# publish1.net
KiCad netlist of a schematic drawn in EAGLE
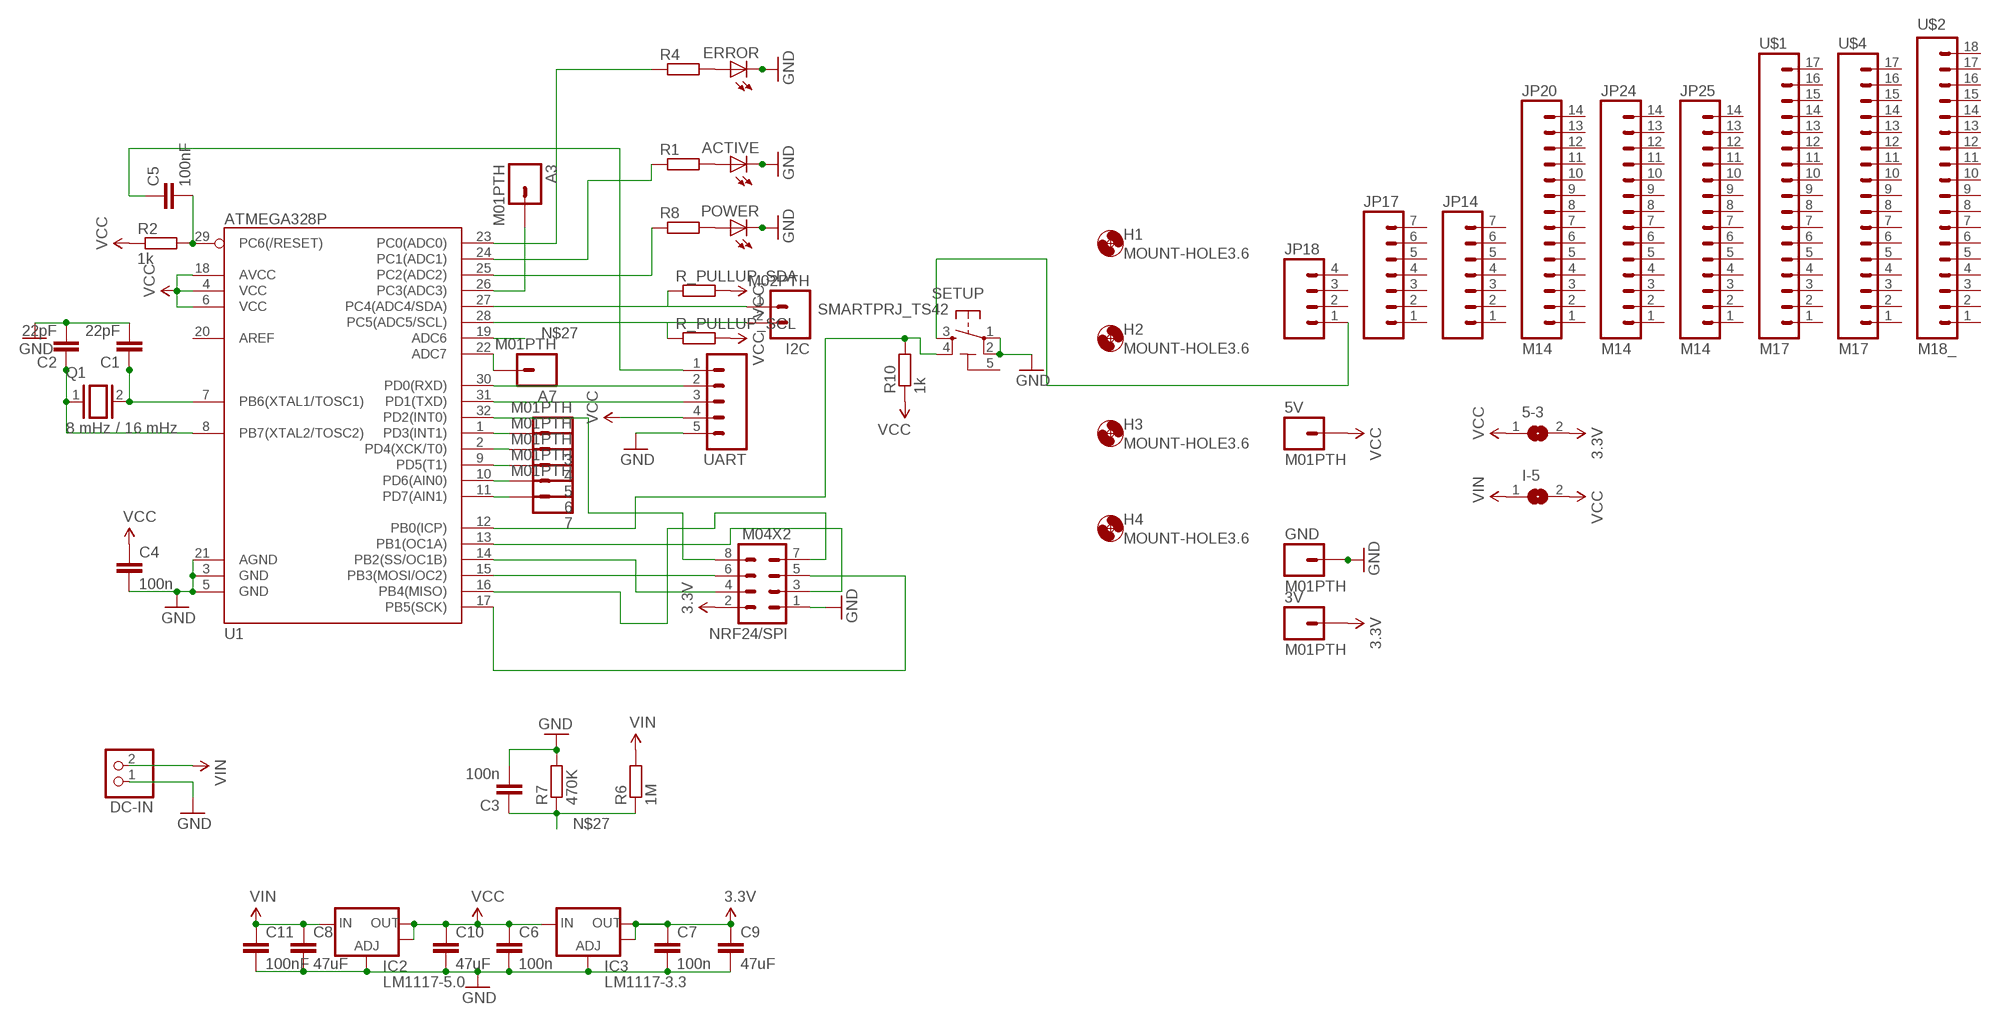
[diagram p0: schematic, sheet 1]

(export (version "E")
  (design (tool "Eeschema 10.0.6"))
  (components
    (comp (ref "3")
      (value "M01PTH")
      (footprint "eagle-import:1X01")
      (libsource (lib "eagle-import") (part "M01PTH"))
    )
    (comp (ref "3V")
      (value "M01PTH")
      (footprint "eagle-import:1X01")
      (libsource (lib "eagle-import") (part "M01PTH"))
    )
    (comp (ref "4")
      (value "M01PTH")
      (footprint "eagle-import:1X01")
      (libsource (lib "eagle-import") (part "M01PTH"))
    )
    (comp (ref "5")
      (value "M01PTH")
      (footprint "eagle-import:1X01")
      (libsource (lib "eagle-import") (part "M01PTH"))
    )
    (comp (ref "5-3")
      (value "JUMPER_SJ")
      (footprint "eagle-import:JUMPER_SJ")
      (libsource (lib "eagle-import") (part "JUMPER_SJ"))
    )
    (comp (ref "5V")
      (value "M01PTH")
      (footprint "eagle-import:1X01")
      (libsource (lib "eagle-import") (part "M01PTH"))
    )
    (comp (ref "6")
      (value "M01PTH")
      (footprint "eagle-import:1X01")
      (libsource (lib "eagle-import") (part "M01PTH"))
    )
    (comp (ref "7")
      (value "M01PTH")
      (footprint "eagle-import:1X01")
      (libsource (lib "eagle-import") (part "M01PTH"))
    )
    (comp (ref "A3")
      (value "M01PTH")
      (footprint "eagle-import:1X01")
      (libsource (lib "eagle-import") (part "M01PTH"))
    )
    (comp (ref "A7")
      (value "M01PTH")
      (footprint "eagle-import:1X01")
      (libsource (lib "eagle-import") (part "M01PTH"))
    )
    (comp (ref "ACTIVE")
      (value "LEDCHIP-LED0805")
      (footprint "eagle-import:CHIP-LED0805")
      (libsource (lib "eagle-import") (part "LEDCHIP-LED0805"))
    )
    (comp (ref "C1")
      (value "22pF")
      (footprint "eagle-import:C0805K")
      (libsource (lib "eagle-import") (part "C-EUC0805K"))
    )
    (comp (ref "C2")
      (value "22pF")
      (footprint "eagle-import:C0805K")
      (libsource (lib "eagle-import") (part "C-EUC0805K"))
    )
    (comp (ref "C3")
      (value "100n")
      (footprint "eagle-import:C0805K")
      (libsource (lib "eagle-import") (part "C-EUC0805K"))
    )
    (comp (ref "C4")
      (value "100n")
      (footprint "eagle-import:C0805K")
      (libsource (lib "eagle-import") (part "C-EUC0805K"))
    )
    (comp (ref "C5")
      (value "100nF")
      (footprint "eagle-import:C0805K")
      (libsource (lib "eagle-import") (part "C-EUC0805K"))
    )
    (comp (ref "C6")
      (value "100n")
      (footprint "eagle-import:C0805K")
      (libsource (lib "eagle-import") (part "C-EUC0805K"))
    )
    (comp (ref "C7")
      (value "100n")
      (footprint "eagle-import:C0805K")
      (libsource (lib "eagle-import") (part "C-EUC0805K"))
    )
    (comp (ref "C8")
      (value "47uF")
      (footprint "eagle-import:1210")
      (libsource (lib "eagle-import") (part "22UF-16V-20%-(1210)"))
    )
    (comp (ref "C9")
      (value "47uF")
      (footprint "eagle-import:1210")
      (libsource (lib "eagle-import") (part "22UF-16V-20%-(1210)"))
    )
    (comp (ref "C10")
      (value "47uF")
      (footprint "eagle-import:1210")
      (libsource (lib "eagle-import") (part "22UF-16V-20%-(1210)"))
    )
    (comp (ref "C11")
      (value "100nF")
      (footprint "eagle-import:C0805K")
      (libsource (lib "eagle-import") (part "C-EUC0805K"))
    )
    (comp (ref "DC-IN")
      (value "PINHD-1X2")
      (footprint "eagle-import:1X02")
      (libsource (lib "eagle-import") (part "PINHD-1X2"))
    )
    (comp (ref "ERROR")
      (value "LEDCHIP-LED0805")
      (footprint "eagle-import:CHIP-LED0805")
      (libsource (lib "eagle-import") (part "LEDCHIP-LED0805"))
    )
    (comp (ref "GND")
      (value "M01PTH")
      (footprint "eagle-import:1X01")
      (libsource (lib "eagle-import") (part "M01PTH"))
    )
    (comp (ref "H1")
      (value "MOUNT-HOLE3.6")
      (footprint "eagle-import:3,6")
      (libsource (lib "eagle-import") (part "MOUNT-HOLE3.6"))
    )
    (comp (ref "H2")
      (value "MOUNT-HOLE3.6")
      (footprint "eagle-import:3,6")
      (libsource (lib "eagle-import") (part "MOUNT-HOLE3.6"))
    )
    (comp (ref "H3")
      (value "MOUNT-HOLE3.6")
      (footprint "eagle-import:3,6")
      (libsource (lib "eagle-import") (part "MOUNT-HOLE3.6"))
    )
    (comp (ref "H4")
      (value "MOUNT-HOLE3.6")
      (footprint "eagle-import:3,6")
      (libsource (lib "eagle-import") (part "MOUNT-HOLE3.6"))
    )
    (comp (ref "I-5")
      (value "JUMPER_SJ")
      (footprint "eagle-import:JUMPER_SJ")
      (libsource (lib "eagle-import") (part "JUMPER_SJ"))
    )
    (comp (ref "I2C")
      (value "M02PTH")
      (footprint "eagle-import:1X02")
      (libsource (lib "eagle-import") (part "M02PTH"))
    )
    (comp (ref "IC2")
      (value "LM1117-5.0")
      (footprint "eagle-import:SOT223")
      (libsource (lib "eagle-import") (part "V_REG_LM1117SOT223"))
    )
    (comp (ref "IC3")
      (value "LM1117-3.3")
      (footprint "eagle-import:SOT223")
      (libsource (lib "eagle-import") (part "V_REG_LM1117SOT223"))
    )
    (comp (ref "JP14")
      (value "M07")
      (footprint "eagle-import:1X07")
      (libsource (lib "eagle-import") (part "M07"))
    )
    (comp (ref "JP17")
      (value "M07")
      (footprint "eagle-import:1X07")
      (libsource (lib "eagle-import") (part "M07"))
    )
    (comp (ref "JP18")
      (value "M04PTH")
      (footprint "eagle-import:1X04")
      (libsource (lib "eagle-import") (part "M04PTH"))
    )
    (comp (ref "JP20")
      (value "M14")
      (footprint "eagle-import:1X14")
      (libsource (lib "eagle-import") (part "M14"))
    )
    (comp (ref "JP24")
      (value "M14")
      (footprint "eagle-import:1X14")
      (libsource (lib "eagle-import") (part "M14"))
    )
    (comp (ref "JP25")
      (value "M14")
      (footprint "eagle-import:1X14")
      (libsource (lib "eagle-import") (part "M14"))
    )
    (comp (ref "NRF24/SPI")
      (value "M04X2")
      (footprint "eagle-import:2X4")
      (libsource (lib "eagle-import") (part "M04X2"))
    )
    (comp (ref "POWER")
      (value "LEDCHIP-LED0805")
      (footprint "eagle-import:CHIP-LED0805")
      (libsource (lib "eagle-import") (part "LEDCHIP-LED0805"))
    )
    (comp (ref "Q1")
      (value "8 mHz / 16 mHz")
      (footprint "eagle-import:QS")
      (libsource (lib "eagle-import") (part "XTAL/S"))
    )
    (comp (ref "R1")
      (value "SMARTPRJ_R-EU_M0805")
      (footprint "eagle-import:SMARTPRJ_M0805")
      (libsource (lib "eagle-import") (part "SMARTPRJ_R-EU_M0805"))
    )
    (comp (ref "R2")
      (value "1k")
      (footprint "eagle-import:SMARTPRJ_M0805")
      (libsource (lib "eagle-import") (part "SMARTPRJ_R-EU_M0805"))
    )
    (comp (ref "R4")
      (value "SMARTPRJ_R-EU_M0805")
      (footprint "eagle-import:SMARTPRJ_M0805")
      (libsource (lib "eagle-import") (part "SMARTPRJ_R-EU_M0805"))
    )
    (comp (ref "R6")
      (value "1M")
      (footprint "eagle-import:SMARTPRJ_M0805")
      (libsource (lib "eagle-import") (part "SMARTPRJ_R-EU_M0805"))
    )
    (comp (ref "R7")
      (value "470K")
      (footprint "eagle-import:SMARTPRJ_M0805")
      (libsource (lib "eagle-import") (part "SMARTPRJ_R-EU_M0805"))
    )
    (comp (ref "R8")
      (value "SMARTPRJ_R-EU_M0805")
      (footprint "eagle-import:SMARTPRJ_M0805")
      (libsource (lib "eagle-import") (part "SMARTPRJ_R-EU_M0805"))
    )
    (comp (ref "R10")
      (value "1k")
      (footprint "eagle-import:SMARTPRJ_M0805")
      (libsource (lib "eagle-import") (part "SMARTPRJ_R-EU_M0805"))
    )
    (comp (ref "R_PULLUP_SCL")
      (value "SMARTPRJ_R-EU_M0805")
      (footprint "eagle-import:SMARTPRJ_M0805")
      (libsource (lib "eagle-import") (part "SMARTPRJ_R-EU_M0805"))
    )
    (comp (ref "R_PULLUP_SDA")
      (value "SMARTPRJ_R-EU_M0805")
      (footprint "eagle-import:SMARTPRJ_M0805")
      (libsource (lib "eagle-import") (part "SMARTPRJ_R-EU_M0805"))
    )
    (comp (ref "SETUP")
      (value "SMARTPRJ_TS42")
      (footprint "eagle-import:SMARTPRJ_TS42")
      (libsource (lib "eagle-import") (part "SMARTPRJ_TS42"))
    )
    (comp (ref "U$1")
      (value "M17")
      (footprint "eagle-import:1X17")
      (libsource (lib "eagle-import") (part "M17"))
    )
    (comp (ref "U$2")
      (value "M18_")
      (footprint "eagle-import:1X18")
      (libsource (lib "eagle-import") (part "M18_"))
    )
    (comp (ref "U$4")
      (value "M17")
      (footprint "eagle-import:1X17")
      (libsource (lib "eagle-import") (part "M17"))
    )
    (comp (ref "U1")
      (value "ATMEGA328P")
      (footprint "eagle-import:TQFP32-08")
      (libsource (lib "eagle-import") (part "ATMEGA328_SMT"))
    )
    (comp (ref "UART")
      (value "M05PTH")
      (footprint "eagle-import:1X05")
      (libsource (lib "eagle-import") (part "M05PTH"))
    )
  )
  (nets
    (net (code "1") (name "/5-GND") (class "Default")
      (node (ref "SETUP") (pin "5") (pinfunction "5-GND_5") (pintype "power_in"))
    )
    (net (code "2") (name "/N$27") (class "Default")
      (node (ref "C3") (pin "1") (pinfunction "1_1") (pintype "passive"))
      (node (ref "R6") (pin "1") (pinfunction "1_1") (pintype "passive"))
      (node (ref "R7") (pin "1") (pinfunction "1_1") (pintype "passive"))
      (node (ref "U1") (pin "19") (pinfunction "ADC6_19") (pintype "bidirectional"))
    )
    (net (code "3") (name "3.3V") (class "Default")
      (node (ref "3V") (pin "1") (pinfunction "1_1") (pintype "passive"))
      (node (ref "5-3") (pin "2") (pinfunction "2_2") (pintype "passive"))
      (node (ref "C7") (pin "1") (pinfunction "1_1") (pintype "passive"))
      (node (ref "C9") (pin "1") (pinfunction "1_1") (pintype "passive"))
      (node (ref "IC3") (pin "2") (pinfunction "OUT_2") (pintype "output"))
      (node (ref "IC3") (pin "4") (pinfunction "OUT_4") (pintype "output"))
      (node (ref "NRF24/SPI") (pin "2") (pinfunction "2_2") (pintype "passive"))
    )
    (net (code "4") (name "GND") (class "Default")
      (node (ref "ACTIVE") (pin "C") (pinfunction "C_C") (pintype "passive"))
      (node (ref "C1") (pin "2") (pinfunction "2_2") (pintype "passive"))
      (node (ref "C10") (pin "2") (pinfunction "2_2") (pintype "passive"))
      (node (ref "C11") (pin "2") (pinfunction "2_2") (pintype "passive"))
      (node (ref "C2") (pin "2") (pinfunction "2_2") (pintype "passive"))
      (node (ref "C3") (pin "2") (pinfunction "2_2") (pintype "passive"))
      (node (ref "C4") (pin "2") (pinfunction "2_2") (pintype "passive"))
      (node (ref "C6") (pin "2") (pinfunction "2_2") (pintype "passive"))
      (node (ref "C7") (pin "2") (pinfunction "2_2") (pintype "passive"))
      (node (ref "C8") (pin "2") (pinfunction "2_2") (pintype "passive"))
      (node (ref "C9") (pin "2") (pinfunction "2_2") (pintype "passive"))
      (node (ref "DC-IN") (pin "1") (pinfunction "1_1") (pintype "passive"))
      (node (ref "ERROR") (pin "C") (pinfunction "C_C") (pintype "passive"))
      (node (ref "GND") (pin "1") (pinfunction "1_1") (pintype "passive"))
      (node (ref "IC2") (pin "1") (pinfunction "ADJ_1") (pintype "input"))
      (node (ref "IC3") (pin "1") (pinfunction "ADJ_1") (pintype "input"))
      (node (ref "NRF24/SPI") (pin "1") (pinfunction "1_1") (pintype "passive"))
      (node (ref "POWER") (pin "C") (pinfunction "C_C") (pintype "passive"))
      (node (ref "R7") (pin "2") (pinfunction "2_2") (pintype "passive"))
      (node (ref "SETUP") (pin "1") (pinfunction "1_1") (pintype "passive"))
      (node (ref "SETUP") (pin "2") (pinfunction "2_2") (pintype "passive"))
      (node (ref "U1") (pin "21") (pinfunction "AGND_21") (pintype "bidirectional"))
      (node (ref "U1") (pin "3") (pinfunction "GND_3") (pintype "bidirectional"))
      (node (ref "U1") (pin "5") (pinfunction "GND_5") (pintype "bidirectional"))
      (node (ref "UART") (pin "5") (pinfunction "5_5") (pintype "passive"))
    )
    (net (code "5") (name "Net-(ACTIVE-PadA)") (class "Default")
      (node (ref "ACTIVE") (pin "A") (pinfunction "A_A") (pintype "passive"))
      (node (ref "R1") (pin "2") (pinfunction "2_2") (pintype "passive"))
    )
    (net (code "6") (name "Net-(C5-Pad1)") (class "Default")
      (node (ref "C5") (pin "1") (pinfunction "1_1") (pintype "passive"))
      (node (ref "UART") (pin "1") (pinfunction "1_1") (pintype "passive"))
    )
    (net (code "7") (name "Net-(ERROR-PadA)") (class "Default")
      (node (ref "ERROR") (pin "A") (pinfunction "A_A") (pintype "passive"))
      (node (ref "R4") (pin "2") (pinfunction "2_2") (pintype "passive"))
    )
    (net (code "8") (name "Net-(JP18-Pad1)") (class "Default")
      (node (ref "JP18") (pin "1") (pinfunction "1_1") (pintype "passive"))
      (node (ref "SETUP") (pin "3") (pinfunction "3_3") (pintype "passive"))
    )
    (net (code "9") (name "Net-(POWER-PadA)") (class "Default")
      (node (ref "POWER") (pin "A") (pinfunction "A_A") (pintype "passive"))
      (node (ref "R8") (pin "2") (pinfunction "2_2") (pintype "passive"))
    )
    (net (code "10") (name "Net-(U1-ADC7)") (class "Default")
      (node (ref "A7") (pin "1") (pinfunction "1_1") (pintype "passive"))
      (node (ref "U1") (pin "22") (pinfunction "ADC7_22") (pintype "bidirectional"))
    )
    (net (code "11") (name "Net-(U1-PB0(ICP))") (class "Default")
      (node (ref "R10") (pin "2") (pinfunction "2_2") (pintype "passive"))
      (node (ref "SETUP") (pin "4") (pinfunction "4_4") (pintype "passive"))
      (node (ref "U1") (pin "12") (pinfunction "PB0(ICP)_12") (pintype "bidirectional"))
    )
    (net (code "12") (name "Net-(U1-PB1(OC1A))") (class "Default")
      (node (ref "NRF24/SPI") (pin "3") (pinfunction "3_3") (pintype "passive"))
      (node (ref "U1") (pin "13") (pinfunction "PB1(OC1A)_13") (pintype "bidirectional"))
    )
    (net (code "13") (name "Net-(U1-PB2(SS{slash}OC1B))") (class "Default")
      (node (ref "NRF24/SPI") (pin "4") (pinfunction "4_4") (pintype "passive"))
      (node (ref "U1") (pin "14") (pinfunction "PB2(SS/OC1B)_14") (pintype "bidirectional"))
    )
    (net (code "14") (name "Net-(U1-PB3(MOSI{slash}OC2))") (class "Default")
      (node (ref "NRF24/SPI") (pin "6") (pinfunction "6_6") (pintype "passive"))
      (node (ref "U1") (pin "15") (pinfunction "PB3(MOSI/OC2)_15") (pintype "bidirectional"))
    )
    (net (code "15") (name "Net-(U1-PB4(MISO))") (class "Default")
      (node (ref "NRF24/SPI") (pin "7") (pinfunction "7_7") (pintype "passive"))
      (node (ref "U1") (pin "16") (pinfunction "PB4(MISO)_16") (pintype "bidirectional"))
    )
    (net (code "16") (name "Net-(U1-PB5(SCK))") (class "Default")
      (node (ref "NRF24/SPI") (pin "5") (pinfunction "5_5") (pintype "passive"))
      (node (ref "U1") (pin "17") (pinfunction "PB5(SCK)_17") (pintype "bidirectional"))
    )
    (net (code "17") (name "Net-(U1-PB6(XTAL1{slash}TOSC1))") (class "Default")
      (node (ref "C1") (pin "1") (pinfunction "1_1") (pintype "passive"))
      (node (ref "Q1") (pin "2") (pinfunction "2_2") (pintype "passive"))
      (node (ref "U1") (pin "7") (pinfunction "PB6(XTAL1/TOSC1)_7") (pintype "bidirectional"))
    )
    (net (code "18") (name "Net-(U1-PB7(XTAL2{slash}TOSC2))") (class "Default")
      (node (ref "C2") (pin "1") (pinfunction "1_1") (pintype "passive"))
      (node (ref "Q1") (pin "1") (pinfunction "1_1") (pintype "passive"))
      (node (ref "U1") (pin "8") (pinfunction "PB7(XTAL2/TOSC2)_8") (pintype "bidirectional"))
    )
    (net (code "19") (name "Net-(U1-PC0(ADC0))") (class "Default")
      (node (ref "R4") (pin "1") (pinfunction "1_1") (pintype "passive"))
      (node (ref "U1") (pin "23") (pinfunction "PC0(ADC0)_23") (pintype "bidirectional"))
    )
    (net (code "20") (name "Net-(U1-PC1(ADC1))") (class "Default")
      (node (ref "R1") (pin "1") (pinfunction "1_1") (pintype "passive"))
      (node (ref "U1") (pin "24") (pinfunction "PC1(ADC1)_24") (pintype "bidirectional"))
    )
    (net (code "21") (name "Net-(U1-PC2(ADC2))") (class "Default")
      (node (ref "R8") (pin "1") (pinfunction "1_1") (pintype "passive"))
      (node (ref "U1") (pin "25") (pinfunction "PC2(ADC2)_25") (pintype "bidirectional"))
    )
    (net (code "22") (name "Net-(U1-PC3(ADC3))") (class "Default")
      (node (ref "A3") (pin "1") (pinfunction "1_1") (pintype "passive"))
      (node (ref "U1") (pin "26") (pinfunction "PC3(ADC3)_26") (pintype "bidirectional"))
    )
    (net (code "23") (name "Net-(U1-PC4(ADC4{slash}SDA))") (class "Default")
      (node (ref "I2C") (pin "1") (pinfunction "1_1") (pintype "passive"))
      (node (ref "R_PULLUP_SDA") (pin "1") (pinfunction "1_1") (pintype "passive"))
      (node (ref "U1") (pin "27") (pinfunction "PC4(ADC4/SDA)_27") (pintype "bidirectional"))
    )
    (net (code "24") (name "Net-(U1-PC5(ADC5{slash}SCL))") (class "Default")
      (node (ref "I2C") (pin "2") (pinfunction "2_2") (pintype "passive"))
      (node (ref "R_PULLUP_SCL") (pin "1") (pinfunction "1_1") (pintype "passive"))
      (node (ref "U1") (pin "28") (pinfunction "PC5(ADC5/SCL)_28") (pintype "bidirectional"))
    )
    (net (code "25") (name "Net-(U1-PC6({slash}RESET))") (class "Default")
      (node (ref "C5") (pin "2") (pinfunction "2_2") (pintype "passive"))
      (node (ref "R2") (pin "2") (pinfunction "2_2") (pintype "passive"))
      (node (ref "U1") (pin "29") (pinfunction "PC6(/RESET)_29") (pintype "bidirectional"))
    )
    (net (code "26") (name "Net-(U1-PD0(RXD))") (class "Default")
      (node (ref "U1") (pin "30") (pinfunction "PD0(RXD)_30") (pintype "bidirectional"))
      (node (ref "UART") (pin "2") (pinfunction "2_2") (pintype "passive"))
    )
    (net (code "27") (name "Net-(U1-PD1(TXD))") (class "Default")
      (node (ref "U1") (pin "31") (pinfunction "PD1(TXD)_31") (pintype "bidirectional"))
      (node (ref "UART") (pin "3") (pinfunction "3_3") (pintype "passive"))
    )
    (net (code "28") (name "Net-(U1-PD2(INT0))") (class "Default")
      (node (ref "NRF24/SPI") (pin "8") (pinfunction "8_8") (pintype "passive"))
      (node (ref "U1") (pin "32") (pinfunction "PD2(INT0)_32") (pintype "bidirectional"))
    )
    (net (code "29") (name "Net-(U1-PD3(INT1))") (class "Default")
      (node (ref "3") (pin "1") (pinfunction "1_1") (pintype "passive"))
      (node (ref "U1") (pin "1") (pinfunction "PD3(INT1)_1") (pintype "bidirectional"))
    )
    (net (code "30") (name "Net-(U1-PD4(XCK{slash}T0))") (class "Default")
      (node (ref "4") (pin "1") (pinfunction "1_1") (pintype "passive"))
      (node (ref "U1") (pin "2") (pinfunction "PD4(XCK/T0)_2") (pintype "bidirectional"))
    )
    (net (code "31") (name "Net-(U1-PD5(T1))") (class "Default")
      (node (ref "5") (pin "1") (pinfunction "1_1") (pintype "passive"))
      (node (ref "U1") (pin "9") (pinfunction "PD5(T1)_9") (pintype "bidirectional"))
    )
    (net (code "32") (name "Net-(U1-PD6(AIN0))") (class "Default")
      (node (ref "6") (pin "1") (pinfunction "1_1") (pintype "passive"))
      (node (ref "U1") (pin "10") (pinfunction "PD6(AIN0)_10") (pintype "bidirectional"))
    )
    (net (code "33") (name "Net-(U1-PD7(AIN1))") (class "Default")
      (node (ref "7") (pin "1") (pinfunction "1_1") (pintype "passive"))
      (node (ref "U1") (pin "11") (pinfunction "PD7(AIN1)_11") (pintype "bidirectional"))
    )
    (net (code "34") (name "VCC") (class "Default")
      (node (ref "5-3") (pin "1") (pinfunction "1_1") (pintype "passive"))
      (node (ref "5V") (pin "1") (pinfunction "1_1") (pintype "passive"))
      (node (ref "C10") (pin "1") (pinfunction "1_1") (pintype "passive"))
      (node (ref "C4") (pin "1") (pinfunction "1_1") (pintype "passive"))
      (node (ref "C6") (pin "1") (pinfunction "1_1") (pintype "passive"))
      (node (ref "I-5") (pin "2") (pinfunction "2_2") (pintype "passive"))
      (node (ref "IC2") (pin "2") (pinfunction "OUT_2") (pintype "output"))
      (node (ref "IC2") (pin "4") (pinfunction "OUT_4") (pintype "output"))
      (node (ref "IC3") (pin "3") (pinfunction "IN_3") (pintype "input"))
      (node (ref "R10") (pin "1") (pinfunction "1_1") (pintype "passive"))
      (node (ref "R2") (pin "1") (pinfunction "1_1") (pintype "passive"))
      (node (ref "R_PULLUP_SCL") (pin "2") (pinfunction "2_2") (pintype "passive"))
      (node (ref "R_PULLUP_SDA") (pin "2") (pinfunction "2_2") (pintype "passive"))
      (node (ref "U1") (pin "18") (pinfunction "AVCC_18") (pintype "bidirectional"))
      (node (ref "U1") (pin "4") (pinfunction "VCC_4") (pintype "bidirectional"))
      (node (ref "U1") (pin "6") (pinfunction "VCC_6") (pintype "bidirectional"))
      (node (ref "UART") (pin "4") (pinfunction "4_4") (pintype "passive"))
    )
    (net (code "35") (name "VIN") (class "Default")
      (node (ref "C11") (pin "1") (pinfunction "1_1") (pintype "passive"))
      (node (ref "C8") (pin "1") (pinfunction "1_1") (pintype "passive"))
      (node (ref "DC-IN") (pin "2") (pinfunction "2_2") (pintype "passive"))
      (node (ref "I-5") (pin "1") (pinfunction "1_1") (pintype "passive"))
      (node (ref "IC2") (pin "3") (pinfunction "IN_3") (pintype "input"))
      (node (ref "R6") (pin "2") (pinfunction "2_2") (pintype "passive"))
    )
    (net (code "36") (name "unconnected-(JP14-Pad1)") (class "Default")
      (node (ref "JP14") (pin "1") (pinfunction "1_1") (pintype "passive"))
    )
    (net (code "37") (name "unconnected-(JP14-Pad2)") (class "Default")
      (node (ref "JP14") (pin "2") (pinfunction "2_2") (pintype "passive"))
    )
    (net (code "38") (name "unconnected-(JP14-Pad3)") (class "Default")
      (node (ref "JP14") (pin "3") (pinfunction "3_3") (pintype "passive"))
    )
    (net (code "39") (name "unconnected-(JP14-Pad4)") (class "Default")
      (node (ref "JP14") (pin "4") (pinfunction "4_4") (pintype "passive"))
    )
    (net (code "40") (name "unconnected-(JP14-Pad5)") (class "Default")
      (node (ref "JP14") (pin "5") (pinfunction "5_5") (pintype "passive"))
    )
    (net (code "41") (name "unconnected-(JP14-Pad6)") (class "Default")
      (node (ref "JP14") (pin "6") (pinfunction "6_6") (pintype "passive"))
    )
    (net (code "42") (name "unconnected-(JP14-Pad7)") (class "Default")
      (node (ref "JP14") (pin "7") (pinfunction "7_7") (pintype "passive"))
    )
    (net (code "43") (name "unconnected-(JP17-Pad1)") (class "Default")
      (node (ref "JP17") (pin "1") (pinfunction "1_1") (pintype "passive"))
    )
    (net (code "44") (name "unconnected-(JP17-Pad2)") (class "Default")
      (node (ref "JP17") (pin "2") (pinfunction "2_2") (pintype "passive"))
    )
    (net (code "45") (name "unconnected-(JP17-Pad3)") (class "Default")
      (node (ref "JP17") (pin "3") (pinfunction "3_3") (pintype "passive"))
    )
    (net (code "46") (name "unconnected-(JP17-Pad4)") (class "Default")
      (node (ref "JP17") (pin "4") (pinfunction "4_4") (pintype "passive"))
    )
    (net (code "47") (name "unconnected-(JP17-Pad5)") (class "Default")
      (node (ref "JP17") (pin "5") (pinfunction "5_5") (pintype "passive"))
    )
    (net (code "48") (name "unconnected-(JP17-Pad6)") (class "Default")
      (node (ref "JP17") (pin "6") (pinfunction "6_6") (pintype "passive"))
    )
    (net (code "49") (name "unconnected-(JP17-Pad7)") (class "Default")
      (node (ref "JP17") (pin "7") (pinfunction "7_7") (pintype "passive"))
    )
    (net (code "50") (name "unconnected-(JP18-Pad2)") (class "Default")
      (node (ref "JP18") (pin "2") (pinfunction "2_2") (pintype "passive"))
    )
    (net (code "51") (name "unconnected-(JP18-Pad3)") (class "Default")
      (node (ref "JP18") (pin "3") (pinfunction "3_3") (pintype "passive"))
    )
    (net (code "52") (name "unconnected-(JP18-Pad4)") (class "Default")
      (node (ref "JP18") (pin "4") (pinfunction "4_4") (pintype "passive"))
    )
    (net (code "53") (name "unconnected-(JP20-Pad1)") (class "Default")
      (node (ref "JP20") (pin "1") (pinfunction "1_1") (pintype "passive"))
    )
    (net (code "54") (name "unconnected-(JP20-Pad2)") (class "Default")
      (node (ref "JP20") (pin "2") (pinfunction "2_2") (pintype "passive"))
    )
    (net (code "55") (name "unconnected-(JP20-Pad3)") (class "Default")
      (node (ref "JP20") (pin "3") (pinfunction "3_3") (pintype "passive"))
    )
    (net (code "56") (name "unconnected-(JP20-Pad4)") (class "Default")
      (node (ref "JP20") (pin "4") (pinfunction "4_4") (pintype "passive"))
    )
    (net (code "57") (name "unconnected-(JP20-Pad5)") (class "Default")
      (node (ref "JP20") (pin "5") (pinfunction "5_5") (pintype "passive"))
    )
    (net (code "58") (name "unconnected-(JP20-Pad6)") (class "Default")
      (node (ref "JP20") (pin "6") (pinfunction "6_6") (pintype "passive"))
    )
    (net (code "59") (name "unconnected-(JP20-Pad7)") (class "Default")
      (node (ref "JP20") (pin "7") (pinfunction "7_7") (pintype "passive"))
    )
    (net (code "60") (name "unconnected-(JP20-Pad8)") (class "Default")
      (node (ref "JP20") (pin "8") (pinfunction "8_8") (pintype "passive"))
    )
    (net (code "61") (name "unconnected-(JP20-Pad9)") (class "Default")
      (node (ref "JP20") (pin "9") (pinfunction "9_9") (pintype "passive"))
    )
    (net (code "62") (name "unconnected-(JP20-Pad10)") (class "Default")
      (node (ref "JP20") (pin "10") (pinfunction "10_10") (pintype "passive"))
    )
    (net (code "63") (name "unconnected-(JP20-Pad11)") (class "Default")
      (node (ref "JP20") (pin "11") (pinfunction "11_11") (pintype "passive"))
    )
    (net (code "64") (name "unconnected-(JP20-Pad12)") (class "Default")
      (node (ref "JP20") (pin "12") (pinfunction "12_12") (pintype "passive"))
    )
    (net (code "65") (name "unconnected-(JP20-Pad13)") (class "Default")
      (node (ref "JP20") (pin "13") (pinfunction "13_13") (pintype "passive"))
    )
    (net (code "66") (name "unconnected-(JP20-Pad14)") (class "Default")
      (node (ref "JP20") (pin "14") (pinfunction "14_14") (pintype "passive"))
    )
    (net (code "67") (name "unconnected-(JP24-Pad1)") (class "Default")
      (node (ref "JP24") (pin "1") (pinfunction "1_1") (pintype "passive"))
    )
    (net (code "68") (name "unconnected-(JP24-Pad2)") (class "Default")
      (node (ref "JP24") (pin "2") (pinfunction "2_2") (pintype "passive"))
    )
    (net (code "69") (name "unconnected-(JP24-Pad3)") (class "Default")
      (node (ref "JP24") (pin "3") (pinfunction "3_3") (pintype "passive"))
    )
    (net (code "70") (name "unconnected-(JP24-Pad4)") (class "Default")
      (node (ref "JP24") (pin "4") (pinfunction "4_4") (pintype "passive"))
    )
    (net (code "71") (name "unconnected-(JP24-Pad5)") (class "Default")
      (node (ref "JP24") (pin "5") (pinfunction "5_5") (pintype "passive"))
    )
    (net (code "72") (name "unconnected-(JP24-Pad6)") (class "Default")
      (node (ref "JP24") (pin "6") (pinfunction "6_6") (pintype "passive"))
    )
    (net (code "73") (name "unconnected-(JP24-Pad7)") (class "Default")
      (node (ref "JP24") (pin "7") (pinfunction "7_7") (pintype "passive"))
    )
    (net (code "74") (name "unconnected-(JP24-Pad8)") (class "Default")
      (node (ref "JP24") (pin "8") (pinfunction "8_8") (pintype "passive"))
    )
    (net (code "75") (name "unconnected-(JP24-Pad9)") (class "Default")
      (node (ref "JP24") (pin "9") (pinfunction "9_9") (pintype "passive"))
    )
    (net (code "76") (name "unconnected-(JP24-Pad10)") (class "Default")
      (node (ref "JP24") (pin "10") (pinfunction "10_10") (pintype "passive"))
    )
    (net (code "77") (name "unconnected-(JP24-Pad11)") (class "Default")
      (node (ref "JP24") (pin "11") (pinfunction "11_11") (pintype "passive"))
    )
    (net (code "78") (name "unconnected-(JP24-Pad12)") (class "Default")
      (node (ref "JP24") (pin "12") (pinfunction "12_12") (pintype "passive"))
    )
    (net (code "79") (name "unconnected-(JP24-Pad13)") (class "Default")
      (node (ref "JP24") (pin "13") (pinfunction "13_13") (pintype "passive"))
    )
    (net (code "80") (name "unconnected-(JP24-Pad14)") (class "Default")
      (node (ref "JP24") (pin "14") (pinfunction "14_14") (pintype "passive"))
    )
    (net (code "81") (name "unconnected-(JP25-Pad1)") (class "Default")
      (node (ref "JP25") (pin "1") (pinfunction "1_1") (pintype "passive"))
    )
    (net (code "82") (name "unconnected-(JP25-Pad2)") (class "Default")
      (node (ref "JP25") (pin "2") (pinfunction "2_2") (pintype "passive"))
    )
    (net (code "83") (name "unconnected-(JP25-Pad3)") (class "Default")
      (node (ref "JP25") (pin "3") (pinfunction "3_3") (pintype "passive"))
    )
    (net (code "84") (name "unconnected-(JP25-Pad4)") (class "Default")
      (node (ref "JP25") (pin "4") (pinfunction "4_4") (pintype "passive"))
    )
    (net (code "85") (name "unconnected-(JP25-Pad5)") (class "Default")
      (node (ref "JP25") (pin "5") (pinfunction "5_5") (pintype "passive"))
    )
    (net (code "86") (name "unconnected-(JP25-Pad6)") (class "Default")
      (node (ref "JP25") (pin "6") (pinfunction "6_6") (pintype "passive"))
    )
    (net (code "87") (name "unconnected-(JP25-Pad7)") (class "Default")
      (node (ref "JP25") (pin "7") (pinfunction "7_7") (pintype "passive"))
    )
    (net (code "88") (name "unconnected-(JP25-Pad8)") (class "Default")
      (node (ref "JP25") (pin "8") (pinfunction "8_8") (pintype "passive"))
    )
    (net (code "89") (name "unconnected-(JP25-Pad9)") (class "Default")
      (node (ref "JP25") (pin "9") (pinfunction "9_9") (pintype "passive"))
    )
    (net (code "90") (name "unconnected-(JP25-Pad10)") (class "Default")
      (node (ref "JP25") (pin "10") (pinfunction "10_10") (pintype "passive"))
    )
    (net (code "91") (name "unconnected-(JP25-Pad11)") (class "Default")
      (node (ref "JP25") (pin "11") (pinfunction "11_11") (pintype "passive"))
    )
    (net (code "92") (name "unconnected-(JP25-Pad12)") (class "Default")
      (node (ref "JP25") (pin "12") (pinfunction "12_12") (pintype "passive"))
    )
    (net (code "93") (name "unconnected-(JP25-Pad13)") (class "Default")
      (node (ref "JP25") (pin "13") (pinfunction "13_13") (pintype "passive"))
    )
    (net (code "94") (name "unconnected-(JP25-Pad14)") (class "Default")
      (node (ref "JP25") (pin "14") (pinfunction "14_14") (pintype "passive"))
    )
    (net (code "95") (name "unconnected-(U$1-Pad1)") (class "Default")
      (node (ref "U$1") (pin "1") (pinfunction "1_1") (pintype "passive"))
    )
    (net (code "96") (name "unconnected-(U$1-Pad2)") (class "Default")
      (node (ref "U$1") (pin "2") (pinfunction "2_2") (pintype "passive"))
    )
    (net (code "97") (name "unconnected-(U$1-Pad3)") (class "Default")
      (node (ref "U$1") (pin "3") (pinfunction "3_3") (pintype "passive"))
    )
    (net (code "98") (name "unconnected-(U$1-Pad4)") (class "Default")
      (node (ref "U$1") (pin "4") (pinfunction "4_4") (pintype "passive"))
    )
    (net (code "99") (name "unconnected-(U$1-Pad5)") (class "Default")
      (node (ref "U$1") (pin "5") (pinfunction "5_5") (pintype "passive"))
    )
    (net (code "100") (name "unconnected-(U$1-Pad6)") (class "Default")
      (node (ref "U$1") (pin "6") (pinfunction "6_6") (pintype "passive"))
    )
    (net (code "101") (name "unconnected-(U$1-Pad7)") (class "Default")
      (node (ref "U$1") (pin "7") (pinfunction "7_7") (pintype "passive"))
    )
    (net (code "102") (name "unconnected-(U$1-Pad8)") (class "Default")
      (node (ref "U$1") (pin "8") (pinfunction "8_8") (pintype "passive"))
    )
    (net (code "103") (name "unconnected-(U$1-Pad9)") (class "Default")
      (node (ref "U$1") (pin "9") (pinfunction "9_9") (pintype "passive"))
    )
    (net (code "104") (name "unconnected-(U$1-Pad10)") (class "Default")
      (node (ref "U$1") (pin "10") (pinfunction "10_10") (pintype "passive"))
    )
    (net (code "105") (name "unconnected-(U$1-Pad11)") (class "Default")
      (node (ref "U$1") (pin "11") (pinfunction "11_11") (pintype "passive"))
    )
    (net (code "106") (name "unconnected-(U$1-Pad12)") (class "Default")
      (node (ref "U$1") (pin "12") (pinfunction "12_12") (pintype "passive"))
    )
    (net (code "107") (name "unconnected-(U$1-Pad13)") (class "Default")
      (node (ref "U$1") (pin "13") (pinfunction "13_13") (pintype "passive"))
    )
    (net (code "108") (name "unconnected-(U$1-Pad14)") (class "Default")
      (node (ref "U$1") (pin "14") (pinfunction "14_14") (pintype "passive"))
    )
    (net (code "109") (name "unconnected-(U$1-Pad15)") (class "Default")
      (node (ref "U$1") (pin "15") (pinfunction "15_15") (pintype "passive"))
    )
    (net (code "110") (name "unconnected-(U$1-Pad16)") (class "Default")
      (node (ref "U$1") (pin "16") (pinfunction "16_16") (pintype "passive"))
    )
    (net (code "111") (name "unconnected-(U$1-Pad17)") (class "Default")
      (node (ref "U$1") (pin "17") (pinfunction "17_17") (pintype "passive"))
    )
    (net (code "112") (name "unconnected-(U$2-Pad1)") (class "Default")
      (node (ref "U$2") (pin "1") (pinfunction "1_1") (pintype "passive"))
    )
    (net (code "113") (name "unconnected-(U$2-Pad2)") (class "Default")
      (node (ref "U$2") (pin "2") (pinfunction "2_2") (pintype "passive"))
    )
    (net (code "114") (name "unconnected-(U$2-Pad3)") (class "Default")
      (node (ref "U$2") (pin "3") (pinfunction "3_3") (pintype "passive"))
    )
    (net (code "115") (name "unconnected-(U$2-Pad4)") (class "Default")
      (node (ref "U$2") (pin "4") (pinfunction "4_4") (pintype "passive"))
    )
    (net (code "116") (name "unconnected-(U$2-Pad5)") (class "Default")
      (node (ref "U$2") (pin "5") (pinfunction "5_5") (pintype "passive"))
    )
    (net (code "117") (name "unconnected-(U$2-Pad6)") (class "Default")
      (node (ref "U$2") (pin "6") (pinfunction "6_6") (pintype "passive"))
    )
    (net (code "118") (name "unconnected-(U$2-Pad7)") (class "Default")
      (node (ref "U$2") (pin "7") (pinfunction "7_7") (pintype "passive"))
    )
    (net (code "119") (name "unconnected-(U$2-Pad8)") (class "Default")
      (node (ref "U$2") (pin "8") (pinfunction "8_8") (pintype "passive"))
    )
    (net (code "120") (name "unconnected-(U$2-Pad9)") (class "Default")
      (node (ref "U$2") (pin "9") (pinfunction "9_9") (pintype "passive"))
    )
    (net (code "121") (name "unconnected-(U$2-Pad10)") (class "Default")
      (node (ref "U$2") (pin "10") (pinfunction "10_10") (pintype "passive"))
    )
    (net (code "122") (name "unconnected-(U$2-Pad11)") (class "Default")
      (node (ref "U$2") (pin "11") (pinfunction "11_11") (pintype "passive"))
    )
    (net (code "123") (name "unconnected-(U$2-Pad12)") (class "Default")
      (node (ref "U$2") (pin "12") (pinfunction "12_12") (pintype "passive"))
    )
    (net (code "124") (name "unconnected-(U$2-Pad13)") (class "Default")
      (node (ref "U$2") (pin "13") (pinfunction "13_13") (pintype "passive"))
    )
    (net (code "125") (name "unconnected-(U$2-Pad14)") (class "Default")
      (node (ref "U$2") (pin "14") (pinfunction "14_14") (pintype "passive"))
    )
    (net (code "126") (name "unconnected-(U$2-Pad15)") (class "Default")
      (node (ref "U$2") (pin "15") (pinfunction "15_15") (pintype "passive"))
    )
    (net (code "127") (name "unconnected-(U$2-Pad16)") (class "Default")
      (node (ref "U$2") (pin "16") (pinfunction "16_16") (pintype "passive"))
    )
    (net (code "128") (name "unconnected-(U$2-Pad17)") (class "Default")
      (node (ref "U$2") (pin "17") (pinfunction "17_17") (pintype "passive"))
    )
    (net (code "129") (name "unconnected-(U$2-Pad18)") (class "Default")
      (node (ref "U$2") (pin "18") (pinfunction "18_18") (pintype "passive"))
    )
    (net (code "130") (name "unconnected-(U$4-Pad1)") (class "Default")
      (node (ref "U$4") (pin "1") (pinfunction "1_1") (pintype "passive"))
    )
    (net (code "131") (name "unconnected-(U$4-Pad2)") (class "Default")
      (node (ref "U$4") (pin "2") (pinfunction "2_2") (pintype "passive"))
    )
    (net (code "132") (name "unconnected-(U$4-Pad3)") (class "Default")
      (node (ref "U$4") (pin "3") (pinfunction "3_3") (pintype "passive"))
    )
    (net (code "133") (name "unconnected-(U$4-Pad4)") (class "Default")
      (node (ref "U$4") (pin "4") (pinfunction "4_4") (pintype "passive"))
    )
    (net (code "134") (name "unconnected-(U$4-Pad5)") (class "Default")
      (node (ref "U$4") (pin "5") (pinfunction "5_5") (pintype "passive"))
    )
    (net (code "135") (name "unconnected-(U$4-Pad6)") (class "Default")
      (node (ref "U$4") (pin "6") (pinfunction "6_6") (pintype "passive"))
    )
    (net (code "136") (name "unconnected-(U$4-Pad7)") (class "Default")
      (node (ref "U$4") (pin "7") (pinfunction "7_7") (pintype "passive"))
    )
    (net (code "137") (name "unconnected-(U$4-Pad8)") (class "Default")
      (node (ref "U$4") (pin "8") (pinfunction "8_8") (pintype "passive"))
    )
    (net (code "138") (name "unconnected-(U$4-Pad9)") (class "Default")
      (node (ref "U$4") (pin "9") (pinfunction "9_9") (pintype "passive"))
    )
    (net (code "139") (name "unconnected-(U$4-Pad10)") (class "Default")
      (node (ref "U$4") (pin "10") (pinfunction "10_10") (pintype "passive"))
    )
    (net (code "140") (name "unconnected-(U$4-Pad11)") (class "Default")
      (node (ref "U$4") (pin "11") (pinfunction "11_11") (pintype "passive"))
    )
    (net (code "141") (name "unconnected-(U$4-Pad12)") (class "Default")
      (node (ref "U$4") (pin "12") (pinfunction "12_12") (pintype "passive"))
    )
    (net (code "142") (name "unconnected-(U$4-Pad13)") (class "Default")
      (node (ref "U$4") (pin "13") (pinfunction "13_13") (pintype "passive"))
    )
    (net (code "143") (name "unconnected-(U$4-Pad14)") (class "Default")
      (node (ref "U$4") (pin "14") (pinfunction "14_14") (pintype "passive"))
    )
    (net (code "144") (name "unconnected-(U$4-Pad15)") (class "Default")
      (node (ref "U$4") (pin "15") (pinfunction "15_15") (pintype "passive"))
    )
    (net (code "145") (name "unconnected-(U$4-Pad16)") (class "Default")
      (node (ref "U$4") (pin "16") (pinfunction "16_16") (pintype "passive"))
    )
    (net (code "146") (name "unconnected-(U$4-Pad17)") (class "Default")
      (node (ref "U$4") (pin "17") (pinfunction "17_17") (pintype "passive"))
    )
    (net (code "147") (name "unconnected-(U1-AREF-Pad20)") (class "Default")
      (node (ref "U1") (pin "20") (pinfunction "AREF_20") (pintype "bidirectional"))
    )
  )
)
